# part_1_2020-12-24_12-20-03.net
KiCad netlist of a schematic drawn in Altium Designer
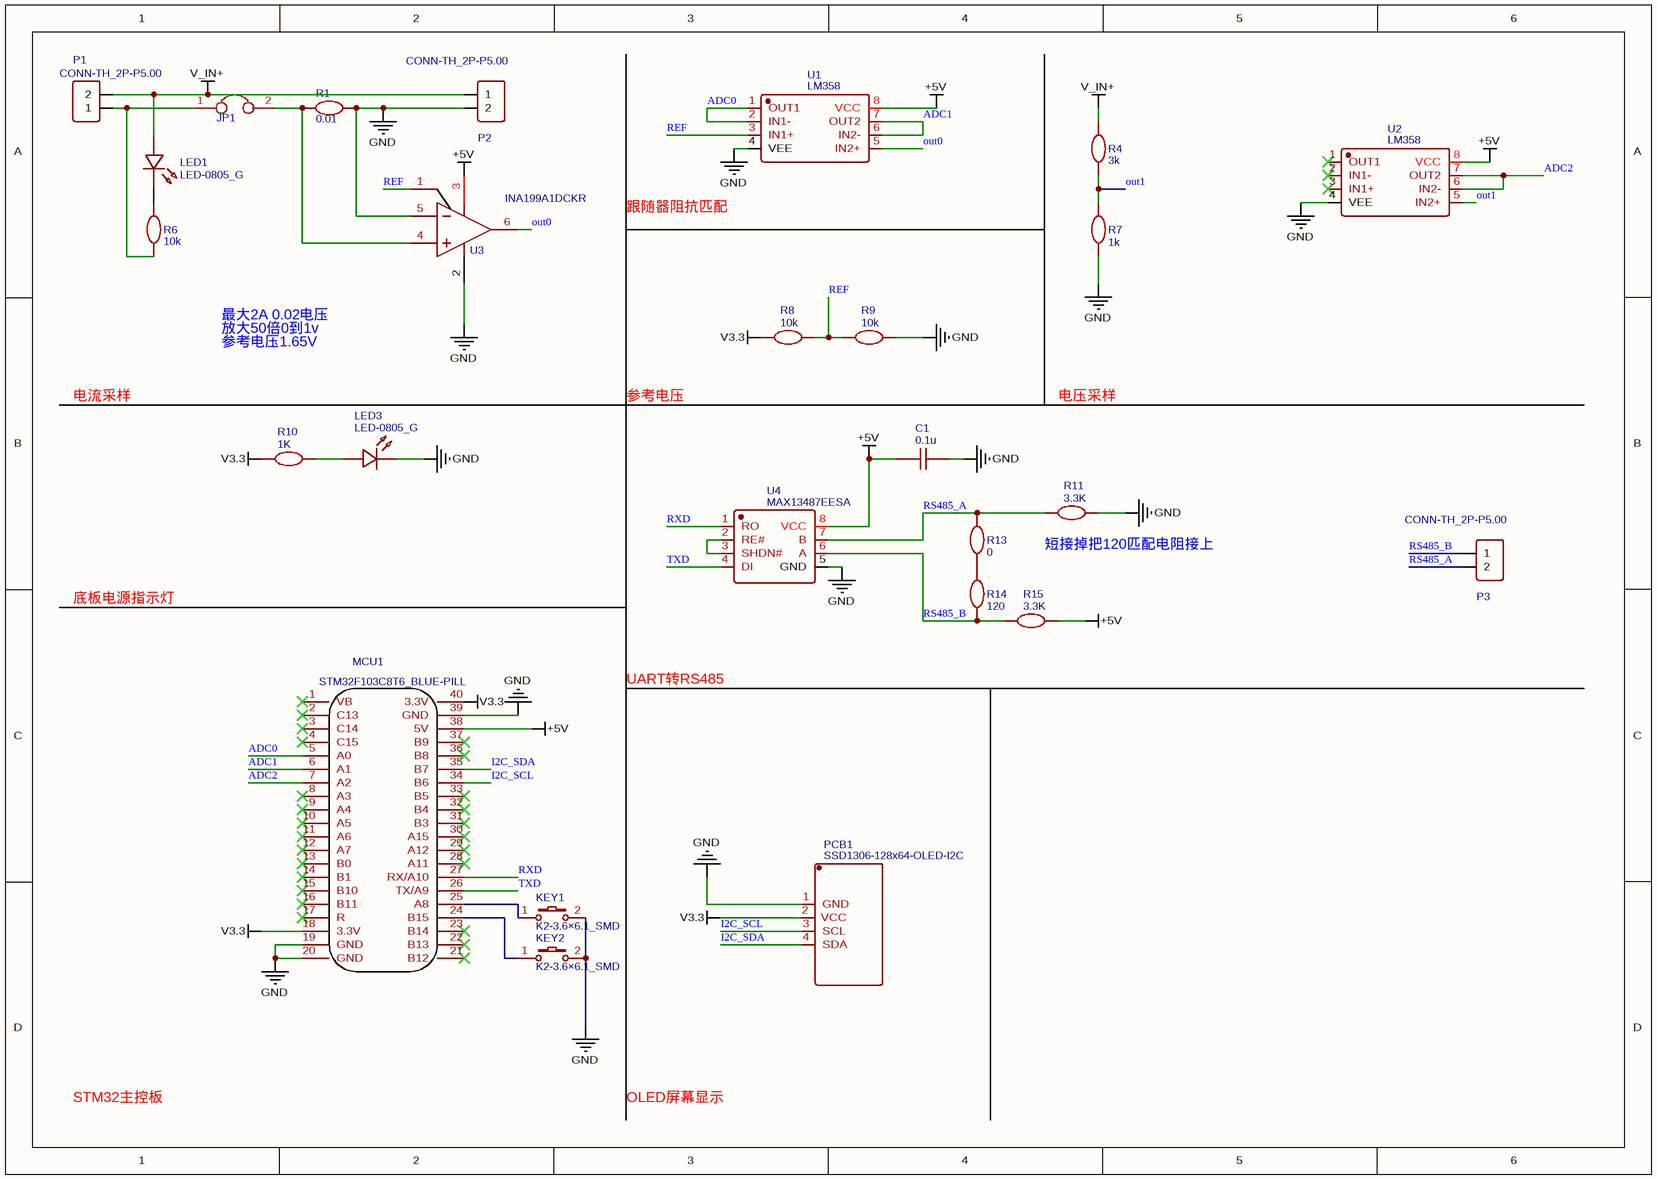
[diagram p0: part_1_2020-12-24_12-20-03.schdoc]

(export (version "E")
  (design (tool "Eeschema 10.0.6"))
  (components
    (comp (ref "C1")
      (value "0.1u")
      (footprint "C0805")
      (fields (field (name "CONTRIBUTOR") "LCEDA_Lib"))
      (libsource (lib "altium-import") (part "root_2_0.1u_"))
    )
    (comp (ref "JP1")
      (value "JUMPER")
      (footprint "HDR-F-2.54_1X2")
      (libsource (lib "altium-import") (part "root_0_JUMPER_"))
    )
    (comp (ref "KEY1")
      (value "K2-3.6×6.1_SMD")
      (footprint "KEY-SMD_2P-L6.2-W3.6-LS8.0")
      (fields
        (field (name "BOM_SUPPLIER PART") "C118141")
        (field (name "BOM_MANUFACTURER PART") "K2-1107ST-A4SW-06")
        (field (name "CONTRIBUTOR") "LCEDA_Lib")
      )
      (libsource (lib "PCB_Project") (part "K2-3.6×6.1_SMD"))
    )
    (comp (ref "KEY2")
      (value "K2-3.6×6.1_SMD")
      (footprint "KEY-SMD_2P-L6.2-W3.6-LS8.0")
      (fields
        (field (name "BOM_SUPPLIER PART") "C118141")
        (field (name "BOM_MANUFACTURER PART") "K2-1107ST-A4SW-06")
        (field (name "CONTRIBUTOR") "LCEDA_Lib")
      )
      (libsource (lib "PCB_Project") (part "K2-3.6×6.1_SMD"))
    )
    (comp (ref "LED1")
      (value "LED-0805_G")
      (footprint "LED0805_GREEN")
      (fields
        (field (name "BOM_MANUFACTURER PART") "19-217/GHC-YR1S2/3T")
        (field (name "BOM_SUPPLIER PART") "C72043")
        (field (name "CONTRIBUTOR") "LCEDA_Lib")
      )
      (libsource (lib "altium-import") (part "root_3_LED-0805_G_"))
    )
    (comp (ref "LED3")
      (value "LED-0805_G")
      (footprint "LED0805_GREEN")
      (fields
        (field (name "BOM_MANUFACTURER PART") "19-217/GHC-YR1S2/3T")
        (field (name "BOM_SUPPLIER PART") "C72043")
        (field (name "CONTRIBUTOR") "LCEDA_Lib")
      )
      (libsource (lib "altium-import") (part "root_0_LED-0805_G_"))
    )
    (comp (ref "MCU1")
      (value "STM32F103C8T6_BLUE-PILL")
      (footprint "STM32F103C8T6_BLUE-PILL")
      (fields (field (name "CONTRIBUTOR") "lzbsuzhou"))
      (libsource (lib "altium-import") (part "root_0_STM32F103C8T6_BLUE-PILL_"))
    )
    (comp (ref "P1")
      (value "CONN-TH_2P-P5.00")
      (footprint "CONN-TH_2P-P5.00")
      (fields (field (name "CONTRIBUTOR") "LCEDA_Lib"))
      (libsource (lib "altium-import") (part "root_2_CONN-TH_2P-P5.00_"))
    )
    (comp (ref "P2")
      (value "CONN-TH_2P-P5.00")
      (footprint "CONN-TH_2P-P5.00")
      (fields (field (name "CONTRIBUTOR") "LCEDA_Lib"))
      (libsource (lib "altium-import") (part "root_0_CONN-TH_2P-P5.00_"))
    )
    (comp (ref "P3")
      (value "CONN-TH_2P-P5.00")
      (footprint "CONN-TH_2P-P5.00")
      (fields (field (name "CONTRIBUTOR") "LCEDA_Lib"))
      (libsource (lib "altium-import") (part "root_0_CONN-TH_2P-P5.00_"))
    )
    (comp (ref "PCB1")
      (value "SSD1306-128x64-OLED-I2C")
      (footprint "SSD1306_GNDVCC")
      (libsource (lib "altium-import") (part "root_0_SSD1306-128x64-OLED-I2C_"))
    )
    (comp (ref "R1")
      (value "0.01")
      (footprint "R2512")
      (fields (field (name "CONTRIBUTOR") "LCEDA_Lib"))
      (libsource (lib "altium-import") (part "root_2_0.01_"))
    )
    (comp (ref "R4")
      (value "3k")
      (footprint "C0805")
      (fields (field (name "CONTRIBUTOR") "LCEDA_Lib"))
      (libsource (lib "altium-import") (part "root_1_3k_"))
    )
    (comp (ref "R6")
      (value "10k")
      (footprint "R0805")
      (fields (field (name "CONTRIBUTOR") "LCEDA_Lib"))
      (libsource (lib "altium-import") (part "root_1_10k_"))
    )
    (comp (ref "R7")
      (value "1k")
      (footprint "C0805")
      (fields (field (name "CONTRIBUTOR") "LCEDA_Lib"))
      (libsource (lib "altium-import") (part "root_1_1k_"))
    )
    (comp (ref "R8")
      (value "10k")
      (footprint "C0805")
      (fields (field (name "CONTRIBUTOR") "LCEDA_Lib"))
      (libsource (lib "altium-import") (part "root_2_10k_"))
    )
    (comp (ref "R9")
      (value "10k")
      (footprint "C0805")
      (fields (field (name "CONTRIBUTOR") "LCEDA_Lib"))
      (libsource (lib "altium-import") (part "root_2_10k_"))
    )
    (comp (ref "R10")
      (value "1K")
      (footprint "R0805")
      (fields (field (name "CONTRIBUTOR") "LCEDA_Lib"))
      (libsource (lib "altium-import") (part "root_2_1K_"))
    )
    (comp (ref "R11")
      (value "3.3K")
      (footprint "R0805")
      (fields (field (name "CONTRIBUTOR") "LCEDA_Lib"))
      (libsource (lib "altium-import") (part "root_2_3.3K_"))
    )
    (comp (ref "R13")
      (value "0")
      (footprint "R0805")
      (fields (field (name "CONTRIBUTOR") "LCEDA_Lib"))
      (libsource (lib "altium-import") (part "root_1_0_"))
    )
    (comp (ref "R14")
      (value "120")
      (footprint "R0805")
      (fields (field (name "CONTRIBUTOR") "LCEDA_Lib"))
      (libsource (lib "altium-import") (part "root_1_120_"))
    )
    (comp (ref "R15")
      (value "3.3K")
      (footprint "R0805")
      (fields (field (name "CONTRIBUTOR") "LCEDA_Lib"))
      (libsource (lib "altium-import") (part "root_0_3.3K_"))
    )
    (comp (ref "U1")
      (value "LM358")
      (footprint "SOP-8_L4.9-W3.9-P1.27-LS6.0-BL")
      (fields (field (name "BOM_SUPPLIER PART") "C328566") (field (name "CONTRIBUTOR") "LCSC"))
      (libsource (lib "altium-import") (part "root_0_LM358_"))
    )
    (comp (ref "U2")
      (value "LM358")
      (footprint "SOP-8_L4.9-W3.9-P1.27-LS6.0-BL")
      (fields (field (name "BOM_SUPPLIER PART") "C328566") (field (name "CONTRIBUTOR") "LCSC"))
      (libsource (lib "altium-import") (part "root_0_LM358_"))
    )
    (comp (ref "U3")
      (value "INA199A1DCKR")
      (footprint "SOT-363_L2.0-W1.3-P0.65-LS2.1-BR")
      (fields
        (field (name "BOM_SUPPLIER PART") "C132098")
        (field (name "BOM_MANUFACTURER PART") "INA199A3DCKR")
        (field (name "CONTRIBUTOR") "LCSC")
      )
      (libsource (lib "altium-import") (part "root_0_INA199A1DCKR_"))
    )
    (comp (ref "U4")
      (value "MAX13487EESA")
      (footprint "SOIC-8_L4.9-W3.9-P1.27-LS6.0-BL")
      (fields (field (name "BOM_SUPPLIER PART") "C18347"))
      (libsource (lib "altium-import") (part "root_0_MAX13487EESA_"))
    )
  )
  (nets
    (net (code "1") (name "+5V") (class "Default")
      (node (ref "C1") (pin "2") (pinfunction "2_2") (pintype "passive"))
      (node (ref "MCU1") (pin "38") (pinfunction "5V_38") (pintype "passive"))
      (node (ref "R15") (pin "2") (pinfunction "2_2") (pintype "passive"))
      (node (ref "U1") (pin "8") (pinfunction "VCC_8") (pintype "passive"))
      (node (ref "U2") (pin "8") (pinfunction "VCC_8") (pintype "passive"))
      (node (ref "U3") (pin "3") (pinfunction "V+_3") (pintype "passive"))
      (node (ref "U4") (pin "8") (pinfunction "VCC_8") (pintype "passive"))
    )
    (net (code "2") (name "/ADC0") (class "Default")
      (node (ref "MCU1") (pin "5") (pinfunction "A0_5") (pintype "passive"))
      (node (ref "U1") (pin "1") (pinfunction "OUT1_1") (pintype "passive"))
      (node (ref "U1") (pin "2") (pinfunction "IN1-_2") (pintype "passive"))
    )
    (net (code "3") (name "/ADC1") (class "Default")
      (node (ref "MCU1") (pin "6") (pinfunction "A1_6") (pintype "passive"))
      (node (ref "U1") (pin "6") (pinfunction "IN2-_6") (pintype "passive"))
      (node (ref "U1") (pin "7") (pinfunction "OUT2_7") (pintype "passive"))
    )
    (net (code "4") (name "/ADC2") (class "Default")
      (node (ref "MCU1") (pin "7") (pinfunction "A2_7") (pintype "passive"))
      (node (ref "U2") (pin "6") (pinfunction "IN2-_6") (pintype "passive"))
      (node (ref "U2") (pin "7") (pinfunction "OUT2_7") (pintype "passive"))
    )
    (net (code "5") (name "/I2C_SCL") (class "Default")
      (node (ref "MCU1") (pin "34") (pinfunction "B6_34") (pintype "passive"))
      (node (ref "PCB1") (pin "3") (pinfunction "SCL_3") (pintype "passive"))
    )
    (net (code "6") (name "/I2C_SDA") (class "Default")
      (node (ref "MCU1") (pin "35") (pinfunction "B7_35") (pintype "passive"))
      (node (ref "PCB1") (pin "4") (pinfunction "SDA_4") (pintype "passive"))
    )
    (net (code "7") (name "/REF") (class "Default")
      (node (ref "R8") (pin "1") (pinfunction "1_1") (pintype "passive"))
      (node (ref "R9") (pin "2") (pinfunction "2_2") (pintype "passive"))
      (node (ref "U1") (pin "3") (pinfunction "IN1+_3") (pintype "passive"))
      (node (ref "U3") (pin "1") (pinfunction "REF_1") (pintype "passive"))
    )
    (net (code "8") (name "/RS485_A") (class "Default")
      (node (ref "P3") (pin "2") (pinfunction "2_2") (pintype "passive"))
      (node (ref "R11") (pin "2") (pinfunction "2_2") (pintype "passive"))
      (node (ref "R13") (pin "2") (pinfunction "2_2") (pintype "passive"))
      (node (ref "U4") (pin "7") (pinfunction "B_7") (pintype "passive"))
    )
    (net (code "9") (name "/RS485_B") (class "Default")
      (node (ref "P3") (pin "1") (pinfunction "1_1") (pintype "passive"))
      (node (ref "R14") (pin "1") (pinfunction "1_1") (pintype "passive"))
      (node (ref "R15") (pin "1") (pinfunction "1_1") (pintype "passive"))
      (node (ref "U4") (pin "6") (pinfunction "A_6") (pintype "passive"))
    )
    (net (code "10") (name "/RXD") (class "Default")
      (node (ref "MCU1") (pin "27") (pinfunction "RX/A10_27") (pintype "passive"))
      (node (ref "U4") (pin "1") (pinfunction "RO_1") (pintype "passive"))
    )
    (net (code "11") (name "/TXD") (class "Default")
      (node (ref "MCU1") (pin "26") (pinfunction "TX/A9_26") (pintype "passive"))
      (node (ref "U4") (pin "4") (pinfunction "DI_4") (pintype "passive"))
    )
    (net (code "12") (name "/out0") (class "Default")
      (node (ref "U1") (pin "5") (pinfunction "IN2+_5") (pintype "passive"))
      (node (ref "U3") (pin "6") (pinfunction "OUT_6") (pintype "passive"))
    )
    (net (code "13") (name "/out1") (class "Default")
      (node (ref "R4") (pin "1") (pinfunction "1_1") (pintype "passive"))
      (node (ref "R7") (pin "2") (pinfunction "2_2") (pintype "passive"))
      (node (ref "U2") (pin "5") (pinfunction "IN2+_5") (pintype "passive"))
    )
    (net (code "14") (name "GND") (class "Default")
      (node (ref "C1") (pin "1") (pinfunction "1_1") (pintype "passive"))
      (node (ref "KEY1") (pin "2") (pinfunction "2_2") (pintype "passive"))
      (node (ref "KEY2") (pin "2") (pinfunction "2_2") (pintype "passive"))
      (node (ref "LED3") (pin "2") (pinfunction "2_2") (pintype "passive"))
      (node (ref "MCU1") (pin "19") (pinfunction "GND_19") (pintype "passive"))
      (node (ref "MCU1") (pin "20") (pinfunction "GND_20") (pintype "passive"))
      (node (ref "MCU1") (pin "39") (pinfunction "GND_39") (pintype "passive"))
      (node (ref "P2") (pin "2") (pinfunction "2_2") (pintype "passive"))
      (node (ref "PCB1") (pin "1") (pinfunction "GND_1") (pintype "passive"))
      (node (ref "R1") (pin "1") (pinfunction "1_1") (pintype "passive"))
      (node (ref "R11") (pin "1") (pinfunction "1_1") (pintype "passive"))
      (node (ref "R7") (pin "1") (pinfunction "1_1") (pintype "passive"))
      (node (ref "R9") (pin "1") (pinfunction "1_1") (pintype "passive"))
      (node (ref "U1") (pin "4") (pinfunction "VEE_4") (pintype "passive"))
      (node (ref "U2") (pin "4") (pinfunction "VEE_4") (pintype "passive"))
      (node (ref "U3") (pin "2") (pinfunction "GND_2") (pintype "passive"))
      (node (ref "U3") (pin "5") (pinfunction "IN-_5") (pintype "passive"))
      (node (ref "U4") (pin "5") (pinfunction "GND_5") (pintype "passive"))
    )
    (net (code "15") (name "Net-(JP1-Pad1)") (class "Default")
      (node (ref "JP1") (pin "1") (pinfunction "1_1") (pintype "passive"))
      (node (ref "P1") (pin "1") (pinfunction "1_1") (pintype "passive"))
      (node (ref "R6") (pin "1") (pinfunction "1_1") (pintype "passive"))
    )
    (net (code "16") (name "Net-(LED1-Pad2)") (class "Default")
      (node (ref "LED1") (pin "2") (pinfunction "2_2") (pintype "passive"))
      (node (ref "R6") (pin "2") (pinfunction "2_2") (pintype "passive"))
    )
    (net (code "17") (name "Net-(LED3-Pad1)") (class "Default")
      (node (ref "LED3") (pin "1") (pinfunction "1_1") (pintype "passive"))
      (node (ref "R10") (pin "1") (pinfunction "1_1") (pintype "passive"))
    )
    (net (code "18") (name "Net-(MCU1-A8)") (class "Default")
      (node (ref "KEY1") (pin "1") (pinfunction "1_1") (pintype "passive"))
      (node (ref "MCU1") (pin "25") (pinfunction "A8_25") (pintype "passive"))
    )
    (net (code "19") (name "Net-(MCU1-B15)") (class "Default")
      (node (ref "KEY2") (pin "1") (pinfunction "1_1") (pintype "passive"))
      (node (ref "MCU1") (pin "24") (pinfunction "B15_24") (pintype "passive"))
    )
    (net (code "20") (name "Net-(R13-Pad1)") (class "Default")
      (node (ref "R13") (pin "1") (pinfunction "1_1") (pintype "passive"))
      (node (ref "R14") (pin "2") (pinfunction "2_2") (pintype "passive"))
    )
    (net (code "21") (name "Net-(U3-IN+)") (class "Default")
      (node (ref "JP1") (pin "2") (pinfunction "2_2") (pintype "passive"))
      (node (ref "R1") (pin "2") (pinfunction "2_2") (pintype "passive"))
      (node (ref "U3") (pin "4") (pinfunction "IN+_4") (pintype "passive"))
    )
    (net (code "22") (name "Net-(U4-RE#)") (class "Default")
      (node (ref "U4") (pin "2") (pinfunction "RE#_2") (pintype "passive"))
      (node (ref "U4") (pin "3") (pinfunction "SHDN#_3") (pintype "passive"))
    )
    (net (code "23") (name "V3.3") (class "Default")
      (node (ref "MCU1") (pin "18") (pinfunction "3.3V_18") (pintype "passive"))
      (node (ref "MCU1") (pin "40") (pinfunction "3.3V_40") (pintype "passive"))
      (node (ref "PCB1") (pin "2") (pinfunction "VCC_2") (pintype "passive"))
      (node (ref "R10") (pin "2") (pinfunction "2_2") (pintype "passive"))
      (node (ref "R8") (pin "2") (pinfunction "2_2") (pintype "passive"))
    )
    (net (code "24") (name "V_IN+") (class "Default")
      (node (ref "LED1") (pin "1") (pinfunction "1_1") (pintype "passive"))
      (node (ref "P1") (pin "2") (pinfunction "2_2") (pintype "passive"))
      (node (ref "P2") (pin "1") (pinfunction "1_1") (pintype "passive"))
      (node (ref "R4") (pin "2") (pinfunction "2_2") (pintype "passive"))
    )
    (net (code "25") (name "unconnected-(MCU1-A3-Pad8)") (class "Default")
      (node (ref "MCU1") (pin "8") (pinfunction "A3_8") (pintype "passive+no_connect"))
    )
    (net (code "26") (name "unconnected-(MCU1-A4-Pad9)") (class "Default")
      (node (ref "MCU1") (pin "9") (pinfunction "A4_9") (pintype "passive+no_connect"))
    )
    (net (code "27") (name "unconnected-(MCU1-A5-Pad10)") (class "Default")
      (node (ref "MCU1") (pin "10") (pinfunction "A5_10") (pintype "passive+no_connect"))
    )
    (net (code "28") (name "unconnected-(MCU1-A6-Pad11)") (class "Default")
      (node (ref "MCU1") (pin "11") (pinfunction "A6_11") (pintype "passive+no_connect"))
    )
    (net (code "29") (name "unconnected-(MCU1-A7-Pad12)") (class "Default")
      (node (ref "MCU1") (pin "12") (pinfunction "A7_12") (pintype "passive+no_connect"))
    )
    (net (code "30") (name "unconnected-(MCU1-A11-Pad28)") (class "Default")
      (node (ref "MCU1") (pin "28") (pinfunction "A11_28") (pintype "passive+no_connect"))
    )
    (net (code "31") (name "unconnected-(MCU1-A12-Pad29)") (class "Default")
      (node (ref "MCU1") (pin "29") (pinfunction "A12_29") (pintype "passive+no_connect"))
    )
    (net (code "32") (name "unconnected-(MCU1-A15-Pad30)") (class "Default")
      (node (ref "MCU1") (pin "30") (pinfunction "A15_30") (pintype "passive+no_connect"))
    )
    (net (code "33") (name "unconnected-(MCU1-B0-Pad13)") (class "Default")
      (node (ref "MCU1") (pin "13") (pinfunction "B0_13") (pintype "passive+no_connect"))
    )
    (net (code "34") (name "unconnected-(MCU1-B1-Pad14)") (class "Default")
      (node (ref "MCU1") (pin "14") (pinfunction "B1_14") (pintype "passive+no_connect"))
    )
    (net (code "35") (name "unconnected-(MCU1-B3-Pad31)") (class "Default")
      (node (ref "MCU1") (pin "31") (pinfunction "B3_31") (pintype "passive+no_connect"))
    )
    (net (code "36") (name "unconnected-(MCU1-B4-Pad32)") (class "Default")
      (node (ref "MCU1") (pin "32") (pinfunction "B4_32") (pintype "passive+no_connect"))
    )
    (net (code "37") (name "unconnected-(MCU1-B5-Pad33)") (class "Default")
      (node (ref "MCU1") (pin "33") (pinfunction "B5_33") (pintype "passive+no_connect"))
    )
    (net (code "38") (name "unconnected-(MCU1-B8-Pad36)") (class "Default")
      (node (ref "MCU1") (pin "36") (pinfunction "B8_36") (pintype "passive+no_connect"))
    )
    (net (code "39") (name "unconnected-(MCU1-B9-Pad37)") (class "Default")
      (node (ref "MCU1") (pin "37") (pinfunction "B9_37") (pintype "passive+no_connect"))
    )
    (net (code "40") (name "unconnected-(MCU1-B10-Pad15)") (class "Default")
      (node (ref "MCU1") (pin "15") (pinfunction "B10_15") (pintype "passive+no_connect"))
    )
    (net (code "41") (name "unconnected-(MCU1-B11-Pad16)") (class "Default")
      (node (ref "MCU1") (pin "16") (pinfunction "B11_16") (pintype "passive+no_connect"))
    )
    (net (code "42") (name "unconnected-(MCU1-B12-Pad21)") (class "Default")
      (node (ref "MCU1") (pin "21") (pinfunction "B12_21") (pintype "passive+no_connect"))
    )
    (net (code "43") (name "unconnected-(MCU1-B13-Pad22)") (class "Default")
      (node (ref "MCU1") (pin "22") (pinfunction "B13_22") (pintype "passive+no_connect"))
    )
    (net (code "44") (name "unconnected-(MCU1-B14-Pad23)") (class "Default")
      (node (ref "MCU1") (pin "23") (pinfunction "B14_23") (pintype "passive+no_connect"))
    )
    (net (code "45") (name "unconnected-(MCU1-C13-Pad2)") (class "Default")
      (node (ref "MCU1") (pin "2") (pinfunction "C13_2") (pintype "passive+no_connect"))
    )
    (net (code "46") (name "unconnected-(MCU1-C14-Pad3)") (class "Default")
      (node (ref "MCU1") (pin "3") (pinfunction "C14_3") (pintype "passive+no_connect"))
    )
    (net (code "47") (name "unconnected-(MCU1-C15-Pad4)") (class "Default")
      (node (ref "MCU1") (pin "4") (pinfunction "C15_4") (pintype "passive+no_connect"))
    )
    (net (code "48") (name "unconnected-(MCU1-R-Pad17)") (class "Default")
      (node (ref "MCU1") (pin "17") (pinfunction "R_17") (pintype "passive+no_connect"))
    )
    (net (code "49") (name "unconnected-(MCU1-VB-Pad1)") (class "Default")
      (node (ref "MCU1") (pin "1") (pinfunction "VB_1") (pintype "passive+no_connect"))
    )
    (net (code "50") (name "unconnected-(U2-IN1+-Pad3)") (class "Default")
      (node (ref "U2") (pin "3") (pinfunction "IN1+_3") (pintype "passive+no_connect"))
    )
    (net (code "51") (name "unconnected-(U2-IN1--Pad2)") (class "Default")
      (node (ref "U2") (pin "2") (pinfunction "IN1-_2") (pintype "passive+no_connect"))
    )
    (net (code "52") (name "unconnected-(U2-OUT1-Pad1)") (class "Default")
      (node (ref "U2") (pin "1") (pinfunction "OUT1_1") (pintype "passive+no_connect"))
    )
  )
)
